# i2c.net
KiCad netlist of a schematic drawn in EAGLE
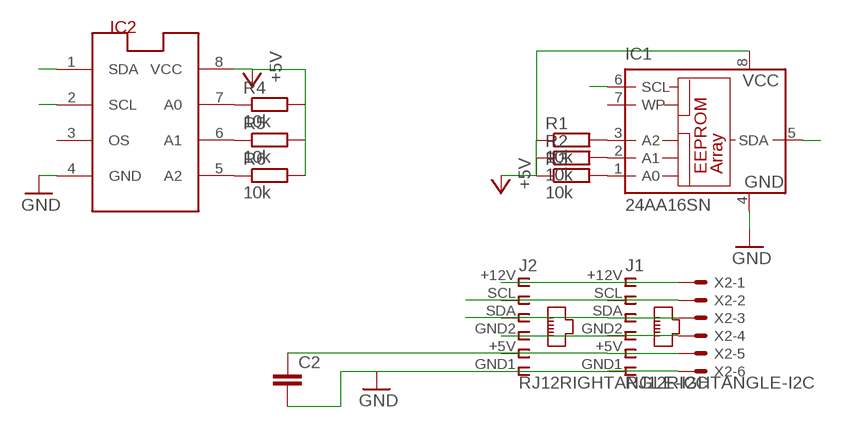
[diagram p0: schematic, sheet 1]

(export (version "E")
  (design (tool "Eeschema 10.0.6"))
  (components
    (comp (ref "C2")
      (value "C-EUC1206")
      (footprint "eagle-import:C1206")
      (libsource (lib "eagle-import") (part "C-EUC1206"))
    )
    (comp (ref "IC1")
      (value "24AA16SN")
      (footprint "eagle-import:SO-08")
      (fields (field (name "MF") "MICROCHIP") (field (name "MPN") "24AA16-I/SN"))
      (libsource (lib "eagle-import") (part "24SNAA16"))
    )
    (comp (ref "IC2")
      (value "LM75_ICN")
      (footprint "eagle-import:SO8_LM75")
      (libsource (lib "eagle-import") (part "LM75_ICN"))
    )
    (comp (ref "J1")
      (value "RJ12RIGHTANGLE-I2C")
      (footprint "eagle-import:RJ12-RIGHTANGLE-I2C")
      (libsource (lib "eagle-import") (part "RJ12RIGHTANGLE-I2C"))
    )
    (comp (ref "J2")
      (value "RJ12RIGHTANGLE-I2C")
      (footprint "eagle-import:RJ12-RIGHTANGLE-I2C")
      (libsource (lib "eagle-import") (part "RJ12RIGHTANGLE-I2C"))
    )
    (comp (ref "R1")
      (value "10k")
      (footprint "eagle-import:M1206")
      (libsource (lib "eagle-import") (part "R-EU_M1206"))
    )
    (comp (ref "R2")
      (value "10k")
      (footprint "eagle-import:M1206")
      (libsource (lib "eagle-import") (part "R-EU_M1206"))
    )
    (comp (ref "R3")
      (value "10k")
      (footprint "eagle-import:M1206")
      (libsource (lib "eagle-import") (part "R-EU_M1206"))
    )
    (comp (ref "R4")
      (value "10k")
      (footprint "eagle-import:M1206")
      (libsource (lib "eagle-import") (part "R-EU_M1206"))
    )
    (comp (ref "R5")
      (value "10k")
      (footprint "eagle-import:M1206")
      (libsource (lib "eagle-import") (part "R-EU_M1206"))
    )
    (comp (ref "R6")
      (value "10k")
      (footprint "eagle-import:M1206")
      (libsource (lib "eagle-import") (part "R-EU_M1206"))
    )
    (comp (ref "X2")
      (value "KK-156-6")
      (footprint "eagle-import:KK-156-6")
      (libsource (lib "eagle-import") (part "KK-156-6"))
    )
  )
  (nets
    (net (code "1") (name "+5V") (class "Default")
      (node (ref "IC1") (pin "8") (pinfunction "VCC_8") (pintype "power_in"))
      (node (ref "IC2") (pin "8") (pinfunction "VCC_8") (pintype "power_in"))
      (node (ref "R1") (pin "1") (pinfunction "1_1") (pintype "passive"))
      (node (ref "R2") (pin "1") (pinfunction "1_1") (pintype "passive"))
      (node (ref "R3") (pin "1") (pinfunction "1_1") (pintype "passive"))
      (node (ref "R4") (pin "2") (pinfunction "2_2") (pintype "passive"))
      (node (ref "R5") (pin "2") (pinfunction "2_2") (pintype "passive"))
      (node (ref "R6") (pin "2") (pinfunction "2_2") (pintype "passive"))
    )
    (net (code "2") (name "/SCL") (class "Default")
      (node (ref "IC1") (pin "6") (pinfunction "SCL_6") (pintype "input"))
      (node (ref "J1") (pin "SCL") (pinfunction "2_SCL") (pintype "bidirectional"))
      (node (ref "J2") (pin "SCL") (pinfunction "2_SCL") (pintype "bidirectional"))
      (node (ref "X2") (pin "2") (pinfunction "S_2") (pintype "passive"))
    )
    (net (code "3") (name "/SDA") (class "Default")
      (node (ref "IC1") (pin "5") (pinfunction "SDA_5") (pintype "bidirectional"))
      (node (ref "J1") (pin "SDA") (pinfunction "3_SDA") (pintype "bidirectional"))
      (node (ref "J2") (pin "SDA") (pinfunction "3_SDA") (pintype "bidirectional"))
      (node (ref "X2") (pin "3") (pinfunction "S_3") (pintype "passive"))
    )
    (net (code "4") (name "GND") (class "Default")
      (node (ref "C2") (pin "2") (pinfunction "2_2") (pintype "passive"))
      (node (ref "IC1") (pin "4") (pinfunction "GND_4") (pintype "power_in"))
      (node (ref "IC2") (pin "4") (pinfunction "GND_4") (pintype "power_in"))
      (node (ref "J1") (pin "GND1") (pinfunction "6_GND1") (pintype "power_in"))
      (node (ref "J2") (pin "GND1") (pinfunction "6_GND1") (pintype "power_in"))
      (node (ref "X2") (pin "6") (pinfunction "S_6") (pintype "passive"))
    )
    (net (code "5") (name "Net-(IC1-A0)") (class "Default")
      (node (ref "IC1") (pin "1") (pinfunction "A0_1") (pintype "input"))
      (node (ref "R3") (pin "2") (pinfunction "2_2") (pintype "passive"))
    )
    (net (code "6") (name "Net-(IC1-A1)") (class "Default")
      (node (ref "IC1") (pin "2") (pinfunction "A1_2") (pintype "input"))
      (node (ref "R2") (pin "2") (pinfunction "2_2") (pintype "passive"))
    )
    (net (code "7") (name "Net-(IC1-A2)") (class "Default")
      (node (ref "IC1") (pin "3") (pinfunction "A2_3") (pintype "input"))
      (node (ref "R1") (pin "2") (pinfunction "2_2") (pintype "passive"))
    )
    (net (code "8") (name "Net-(IC2-A0)") (class "Default")
      (node (ref "IC2") (pin "7") (pinfunction "A0_7") (pintype "input"))
      (node (ref "R4") (pin "1") (pinfunction "1_1") (pintype "passive"))
    )
    (net (code "9") (name "Net-(IC2-A1)") (class "Default")
      (node (ref "IC2") (pin "6") (pinfunction "A1_6") (pintype "input"))
      (node (ref "R5") (pin "1") (pinfunction "1_1") (pintype "passive"))
    )
    (net (code "10") (name "Net-(IC2-A2)") (class "Default")
      (node (ref "IC2") (pin "5") (pinfunction "A2_5") (pintype "input"))
      (node (ref "R6") (pin "1") (pinfunction "1_1") (pintype "passive"))
    )
    (net (code "11") (name "Net-(J1-1)") (class "Default")
      (node (ref "J1") (pin "+12V") (pinfunction "1_+12V") (pintype "power_in"))
      (node (ref "J2") (pin "+12V") (pinfunction "1_+12V") (pintype "power_in"))
      (node (ref "X2") (pin "1") (pinfunction "S_1") (pintype "passive"))
    )
    (net (code "12") (name "Net-(J1-4)") (class "Default")
      (node (ref "J1") (pin "GND2") (pinfunction "4_GND2") (pintype "power_in"))
      (node (ref "J2") (pin "GND2") (pinfunction "4_GND2") (pintype "power_in"))
      (node (ref "X2") (pin "4") (pinfunction "S_4") (pintype "passive"))
    )
    (net (code "13") (name "Net-(J1-5)") (class "Default")
      (node (ref "C2") (pin "1") (pinfunction "1_1") (pintype "passive"))
      (node (ref "J1") (pin "+5V") (pinfunction "5_+5V") (pintype "power_in"))
      (node (ref "J2") (pin "+5V") (pinfunction "5_+5V") (pintype "power_in"))
      (node (ref "X2") (pin "5") (pinfunction "S_5") (pintype "passive"))
    )
    (net (code "14") (name "unconnected-(IC1-WP-Pad7)") (class "Default")
      (node (ref "IC1") (pin "7") (pinfunction "WP_7") (pintype "input"))
    )
    (net (code "15") (name "unconnected-(IC2-OS-Pad3)") (class "Default")
      (node (ref "IC2") (pin "3") (pinfunction "OS_3") (pintype "output"))
    )
    (net (code "16") (name "unconnected-(IC2-SCL-Pad2)") (class "Default")
      (node (ref "IC2") (pin "2") (pinfunction "SCL_2") (pintype "bidirectional"))
    )
    (net (code "17") (name "unconnected-(IC2-SDA-Pad1)") (class "Default")
      (node (ref "IC2") (pin "1") (pinfunction "SDA_1") (pintype "bidirectional"))
    )
  )
)
